# usb.net
KiCad netlist of a schematic drawn in EAGLE
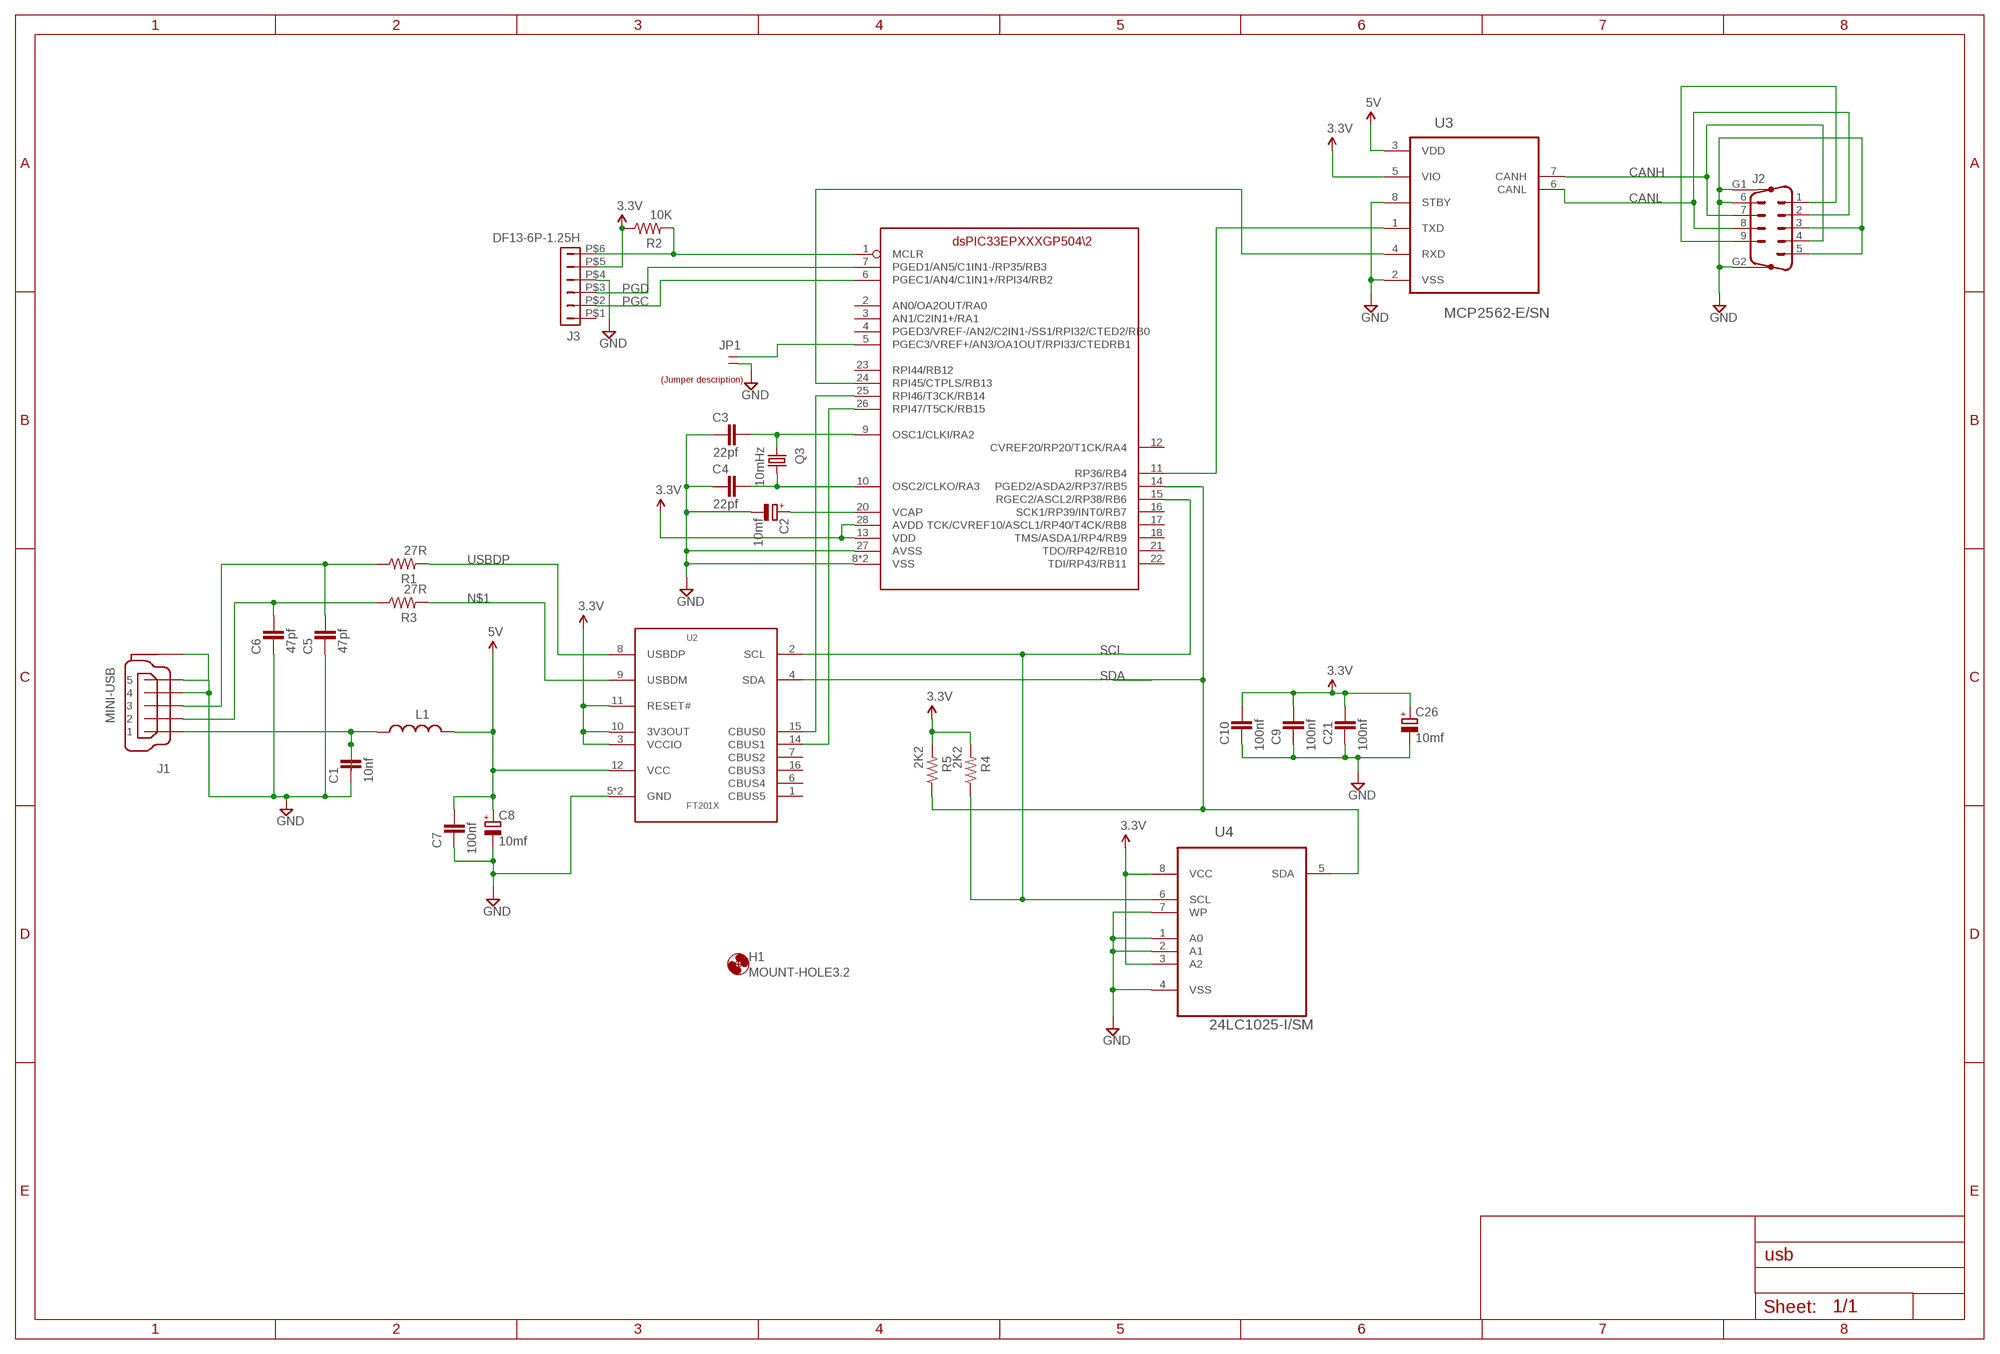
[diagram p0: schematic, sheet 1]

(export (version "E")
  (design (tool "Eeschema 10.0.6"))
  (components
    (comp (ref "C1")
      (value "10nf")
      (footprint "eagle-import:C805")
      (libsource (lib "eagle-import") (part "CAPACITOR_NPOL-0805"))
    )
    (comp (ref "C2")
      (value "10mf")
      (footprint "eagle-import:SMC_A")
      (libsource (lib "eagle-import") (part "CAPACITOR_POL-SMC_A"))
    )
    (comp (ref "C3")
      (value "22pf")
      (footprint "eagle-import:C805")
      (libsource (lib "eagle-import") (part "CAPACITOR_NPOL-0805"))
    )
    (comp (ref "C4")
      (value "22pf")
      (footprint "eagle-import:C805")
      (libsource (lib "eagle-import") (part "CAPACITOR_NPOL-0805"))
    )
    (comp (ref "C5")
      (value "47pf")
      (footprint "eagle-import:C805")
      (libsource (lib "eagle-import") (part "CAPACITOR_NPOL-0805"))
    )
    (comp (ref "C6")
      (value "47pf")
      (footprint "eagle-import:C805")
      (libsource (lib "eagle-import") (part "CAPACITOR_NPOL-0805"))
    )
    (comp (ref "C7")
      (value "100nf")
      (footprint "eagle-import:C805")
      (libsource (lib "eagle-import") (part "CAPACITOR_NPOL-0805"))
    )
    (comp (ref "C8")
      (value "10mf")
      (footprint "eagle-import:SMC_A")
      (libsource (lib "eagle-import") (part "CAPACITOR_POL-SMC_A"))
    )
    (comp (ref "C9")
      (value "100nf")
      (footprint "eagle-import:C805")
      (libsource (lib "eagle-import") (part "CAPACITOR_NPOL-0805"))
    )
    (comp (ref "C10")
      (value "100nf")
      (footprint "eagle-import:C805")
      (libsource (lib "eagle-import") (part "CAPACITOR_NPOL-0805"))
    )
    (comp (ref "C21")
      (value "100nf")
      (footprint "eagle-import:C805")
      (libsource (lib "eagle-import") (part "CAPACITOR_NPOL-0805"))
    )
    (comp (ref "C26")
      (value "10mf")
      (footprint "eagle-import:SMC_A")
      (libsource (lib "eagle-import") (part "CAPACITOR_POL-SMC_A"))
    )
    (comp (ref "H1")
      (value "MOUNT-HOLE3.2")
      (footprint "eagle-import:3,2")
      (libsource (lib "eagle-import") (part "MOUNT-HOLE3.2"))
    )
    (comp (ref "J1")
      (value "MINI-USB")
      (footprint "eagle-import:MINI-USB")
      (libsource (lib "eagle-import") (part "MINI-USB"))
    )
    (comp (ref "J2")
      (value "M09HP")
      (footprint "eagle-import:M09HP")
      (libsource (lib "eagle-import") (part "M09HP"))
    )
    (comp (ref "J3")
      (value "DF13-6P-1.25H")
      (footprint "eagle-import:DF13A-6P-1.25H")
      (libsource (lib "eagle-import") (part "DF13-6P-1.25H"))
    )
    (comp (ref "JP1")
      (value "JUMPER-1X2")
      (footprint "eagle-import:JUMPER-1X2")
      (libsource (lib "eagle-import") (part "JUMPER-1X2"))
    )
    (comp (ref "L1")
      (value "FERRITE-0603")
      (footprint "eagle-import:FB603")
      (libsource (lib "eagle-import") (part "FERRITE-0603"))
    )
    (comp (ref "Q3")
      (value "10mHz")
      (footprint "eagle-import:HC49_S")
      (fields (field (name "PARTNO") "9B-10.000MBBK-B"))
      (libsource (lib "eagle-import") (part "CRYSTALHC49S"))
    )
    (comp (ref "R1")
      (value "27R")
      (footprint "eagle-import:0603-RES")
      (fields (field (name "PARTNO") "ERJ-3GEYJ103V"))
      (libsource (lib "eagle-import") (part "RESISTOR0603-RES"))
    )
    (comp (ref "R2")
      (value "10K")
      (footprint "eagle-import:0603-RES")
      (fields (field (name "PARTNO") "ERJ-3GEYJ103V"))
      (libsource (lib "eagle-import") (part "RESISTOR0603-RES"))
    )
    (comp (ref "R3")
      (value "27R")
      (footprint "eagle-import:0603-RES")
      (fields (field (name "PARTNO") "ERJ-3GEYJ103V"))
      (libsource (lib "eagle-import") (part "RESISTOR0603-RES"))
    )
    (comp (ref "R4")
      (value "2K2")
      (footprint "eagle-import:0603-RES")
      (fields (field (name "PARTNO") "ERJ-3GEYJ103V"))
      (libsource (lib "eagle-import") (part "RESISTOR0603-RES"))
    )
    (comp (ref "R5")
      (value "2K2")
      (footprint "eagle-import:0603-RES")
      (fields (field (name "PARTNO") "ERJ-3GEYJ103V"))
      (libsource (lib "eagle-import") (part "RESISTOR0603-RES"))
    )
    (comp (ref "U$2")
      (value "LABEL_JUMPER_1X2")
      (footprint "eagle-import:JUMP2_DESC")
      (fields (field (name "OFF") "Normal") (field (name "ON") "Reset"))
      (libsource (lib "eagle-import") (part "LABEL_JUMPER_1X2"))
    )
    (comp (ref "U1")
      (value "DSPIC33EPXXXGP502")
      (footprint "eagle-import:SOIC-28")
      (libsource (lib "eagle-import") (part "DSPIC33EPXXXGP502"))
    )
    (comp (ref "U2")
      (value "FT201X")
      (footprint "eagle-import:TSSOP-16")
      (libsource (lib "eagle-import") (part "FT201X"))
    )
    (comp (ref "U3")
      (value "MCP2562-E/SN")
      (footprint "eagle-import:SOIC-8N")
      (libsource (lib "eagle-import") (part "MCP2562-E/SN"))
    )
    (comp (ref "U4")
      (value "24LC1025-I/SM")
      (footprint "eagle-import:SOIC8-N_MC")
      (libsource (lib "eagle-import") (part "24LC1025-I/SM"))
    )
  )
  (nets
    (net (code "1") (name "/CANH") (class "Default")
      (node (ref "J2") (pin "4") (pinfunction "4_4") (pintype "passive"))
      (node (ref "J2") (pin "7") (pinfunction "7_7") (pintype "passive"))
      (node (ref "U3") (pin "7") (pinfunction "CANH_7") (pintype "bidirectional"))
    )
    (net (code "2") (name "/CANL") (class "Default")
      (node (ref "J2") (pin "2") (pinfunction "2_2") (pintype "passive"))
      (node (ref "J2") (pin "8") (pinfunction "8_8") (pintype "passive"))
      (node (ref "U3") (pin "6") (pinfunction "CANL_6") (pintype "bidirectional"))
    )
    (net (code "3") (name "/N$1") (class "Default")
      (node (ref "R3") (pin "2") (pinfunction "2_2") (pintype "passive"))
      (node (ref "U2") (pin "9") (pinfunction "USBDM_9") (pintype "bidirectional"))
    )
    (net (code "4") (name "/PGC") (class "Default")
      (node (ref "J3") (pin "P$2") (pinfunction "2_P$2") (pintype "passive"))
      (node (ref "U1") (pin "6") (pinfunction "PGEC1/AN4/C1IN1+/RPI34/RB2_6") (pintype "bidirectional"))
    )
    (net (code "5") (name "/PGD") (class "Default")
      (node (ref "J3") (pin "P$3") (pinfunction "3_P$3") (pintype "passive"))
      (node (ref "U1") (pin "7") (pinfunction "PGED1/AN5/C1IN1-/RP35/RB3_7") (pintype "bidirectional"))
    )
    (net (code "6") (name "/SCL") (class "Default")
      (node (ref "R4") (pin "1") (pinfunction "1_1") (pintype "passive"))
      (node (ref "U1") (pin "15") (pinfunction "RGEC2/ASCL2/RP38/RB6_15") (pintype "bidirectional"))
      (node (ref "U2") (pin "2") (pinfunction "SCL_2") (pintype "bidirectional"))
      (node (ref "U4") (pin "6") (pinfunction "SCL_6") (pintype "input"))
    )
    (net (code "7") (name "/SDA") (class "Default")
      (node (ref "R5") (pin "1") (pinfunction "1_1") (pintype "passive"))
      (node (ref "U1") (pin "14") (pinfunction "PGED2/ASDA2/RP37/RB5_14") (pintype "bidirectional"))
      (node (ref "U2") (pin "4") (pinfunction "SDA_4") (pintype "bidirectional"))
      (node (ref "U4") (pin "5") (pinfunction "SDA_5") (pintype "bidirectional"))
    )
    (net (code "8") (name "/USBDP") (class "Default")
      (node (ref "R1") (pin "2") (pinfunction "2_2") (pintype "passive"))
      (node (ref "U2") (pin "8") (pinfunction "USBDP_8") (pintype "bidirectional"))
    )
    (net (code "9") (name "3.3V") (class "Default")
      (node (ref "C10") (pin "1") (pinfunction "1_1") (pintype "passive"))
      (node (ref "C21") (pin "1") (pinfunction "1_1") (pintype "passive"))
      (node (ref "C26") (pin "+") (pinfunction "+_+") (pintype "passive"))
      (node (ref "C9") (pin "1") (pinfunction "1_1") (pintype "passive"))
      (node (ref "J3") (pin "P$5") (pinfunction "5_P$5") (pintype "passive"))
      (node (ref "R2") (pin "1") (pinfunction "1_1") (pintype "passive"))
      (node (ref "R4") (pin "2") (pinfunction "2_2") (pintype "passive"))
      (node (ref "R5") (pin "2") (pinfunction "2_2") (pintype "passive"))
      (node (ref "U1") (pin "13") (pinfunction "VDD_13") (pintype "bidirectional"))
      (node (ref "U1") (pin "28") (pinfunction "AVDD_28") (pintype "bidirectional"))
      (node (ref "U2") (pin "10") (pinfunction "3V3OUT_10") (pintype "bidirectional"))
      (node (ref "U2") (pin "11") (pinfunction "RESET#_11") (pintype "bidirectional"))
      (node (ref "U2") (pin "3") (pinfunction "VCCIO_3") (pintype "bidirectional"))
      (node (ref "U3") (pin "5") (pinfunction "VIO_5") (pintype "power_in"))
      (node (ref "U4") (pin "3") (pinfunction "A2_3") (pintype "input"))
      (node (ref "U4") (pin "8") (pinfunction "VCC_8") (pintype "power_in"))
    )
    (net (code "10") (name "5V") (class "Default")
      (node (ref "C7") (pin "1") (pinfunction "1_1") (pintype "passive"))
      (node (ref "C8") (pin "+") (pinfunction "+_+") (pintype "passive"))
      (node (ref "L1") (pin "2") (pinfunction "2_2") (pintype "passive"))
      (node (ref "U2") (pin "12") (pinfunction "VCC_12") (pintype "bidirectional"))
      (node (ref "U3") (pin "3") (pinfunction "VDD_3") (pintype "power_in"))
    )
    (net (code "11") (name "GND") (class "Default")
      (node (ref "C1") (pin "2") (pinfunction "2_2") (pintype "passive"))
      (node (ref "C10") (pin "2") (pinfunction "2_2") (pintype "passive"))
      (node (ref "C2") (pin "-") (pinfunction "-_-") (pintype "passive"))
      (node (ref "C21") (pin "2") (pinfunction "2_2") (pintype "passive"))
      (node (ref "C26") (pin "-") (pinfunction "-_-") (pintype "passive"))
      (node (ref "C3") (pin "2") (pinfunction "2_2") (pintype "passive"))
      (node (ref "C4") (pin "2") (pinfunction "2_2") (pintype "passive"))
      (node (ref "C5") (pin "2") (pinfunction "2_2") (pintype "passive"))
      (node (ref "C6") (pin "2") (pinfunction "2_2") (pintype "passive"))
      (node (ref "C7") (pin "2") (pinfunction "2_2") (pintype "passive"))
      (node (ref "C8") (pin "-") (pinfunction "-_-") (pintype "passive"))
      (node (ref "C9") (pin "2") (pinfunction "2_2") (pintype "passive"))
      (node (ref "J1") (pin "4") (pinfunction "4_4") (pintype "input"))
      (node (ref "J1") (pin "5") (pinfunction "5_5") (pintype "input"))
      (node (ref "J1") (pin "M1") (pinfunction "MOUNT_M1") (pintype "bidirectional"))
      (node (ref "J1") (pin "M2") (pinfunction "MOUNT_M2") (pintype "bidirectional"))
      (node (ref "J1") (pin "M3") (pinfunction "MOUNT_M3") (pintype "bidirectional"))
      (node (ref "J1") (pin "M4") (pinfunction "MOUNT_M4") (pintype "bidirectional"))
      (node (ref "J2") (pin "3") (pinfunction "3_3") (pintype "passive"))
      (node (ref "J2") (pin "5") (pinfunction "5_5") (pintype "passive"))
      (node (ref "J2") (pin "6") (pinfunction "6_6") (pintype "passive"))
      (node (ref "J2") (pin "G1") (pinfunction "G1_G1") (pintype "passive"))
      (node (ref "J2") (pin "G2") (pinfunction "G2_G2") (pintype "passive"))
      (node (ref "J3") (pin "P$4") (pinfunction "4_P$4") (pintype "passive"))
      (node (ref "JP1") (pin "2") (pinfunction "2_2") (pintype "bidirectional"))
      (node (ref "U1") (pin "19") (pinfunction "VSS_19") (pintype "bidirectional"))
      (node (ref "U1") (pin "27") (pinfunction "AVSS_27") (pintype "bidirectional"))
      (node (ref "U1") (pin "8") (pinfunction "VSS_8") (pintype "bidirectional"))
      (node (ref "U2") (pin "13") (pinfunction "GND_13") (pintype "power_in"))
      (node (ref "U2") (pin "5") (pinfunction "GND_5") (pintype "power_in"))
      (node (ref "U3") (pin "2") (pinfunction "VSS_2") (pintype "power_in"))
      (node (ref "U3") (pin "8") (pinfunction "STBY_8") (pintype "input"))
      (node (ref "U4") (pin "1") (pinfunction "A0_1") (pintype "input"))
      (node (ref "U4") (pin "2") (pinfunction "A1_2") (pintype "input"))
      (node (ref "U4") (pin "4") (pinfunction "VSS_4") (pintype "passive"))
      (node (ref "U4") (pin "7") (pinfunction "WP_7") (pintype "input"))
    )
    (net (code "12") (name "Net-(C1-Pad1)") (class "Default")
      (node (ref "C1") (pin "1") (pinfunction "1_1") (pintype "passive"))
      (node (ref "J1") (pin "1") (pinfunction "1_1") (pintype "input"))
      (node (ref "L1") (pin "1") (pinfunction "1_1") (pintype "passive"))
    )
    (net (code "13") (name "Net-(C5-Pad1)") (class "Default")
      (node (ref "C5") (pin "1") (pinfunction "1_1") (pintype "passive"))
      (node (ref "J1") (pin "3") (pinfunction "3_3") (pintype "input"))
      (node (ref "R1") (pin "1") (pinfunction "1_1") (pintype "passive"))
    )
    (net (code "14") (name "Net-(C6-Pad1)") (class "Default")
      (node (ref "C6") (pin "1") (pinfunction "1_1") (pintype "passive"))
      (node (ref "J1") (pin "2") (pinfunction "2_2") (pintype "input"))
      (node (ref "R3") (pin "1") (pinfunction "1_1") (pintype "passive"))
    )
    (net (code "15") (name "Net-(J2-Pad1)") (class "Default")
      (node (ref "J2") (pin "1") (pinfunction "1_1") (pintype "passive"))
      (node (ref "J2") (pin "9") (pinfunction "9_9") (pintype "passive"))
    )
    (net (code "16") (name "Net-(J3-6)") (class "Default")
      (node (ref "J3") (pin "P$6") (pinfunction "6_P$6") (pintype "passive"))
      (node (ref "R2") (pin "2") (pinfunction "2_2") (pintype "passive"))
      (node (ref "U1") (pin "1") (pinfunction "MCLR_1") (pintype "input"))
    )
    (net (code "17") (name "Net-(U1-OSC1{slash}CLKI{slash}RA2)") (class "Default")
      (node (ref "C3") (pin "1") (pinfunction "1_1") (pintype "passive"))
      (node (ref "Q3") (pin "2") (pinfunction "2_2") (pintype "passive"))
      (node (ref "U1") (pin "9") (pinfunction "OSC1/CLKI/RA2_9") (pintype "bidirectional"))
    )
    (net (code "18") (name "Net-(U1-OSC2{slash}CLKO{slash}RA3)") (class "Default")
      (node (ref "C4") (pin "1") (pinfunction "1_1") (pintype "passive"))
      (node (ref "Q3") (pin "1") (pinfunction "1_1") (pintype "passive"))
      (node (ref "U1") (pin "10") (pinfunction "OSC2/CLKO/RA3_10") (pintype "bidirectional"))
    )
    (net (code "19") (name "Net-(U1-PGEC3{slash}VREF+{slash}AN3{slash}OA1OUT{slash}RPI33{slash}CTEDRB1)") (class "Default")
      (node (ref "JP1") (pin "1") (pinfunction "1_1") (pintype "bidirectional"))
      (node (ref "U1") (pin "5") (pinfunction "PGEC3/VREF+/AN3/OA1OUT/RPI33/CTEDRB1_5") (pintype "bidirectional"))
    )
    (net (code "20") (name "Net-(U1-RP36{slash}RB4)") (class "Default")
      (node (ref "U1") (pin "11") (pinfunction "RP36/RB4_11") (pintype "bidirectional"))
      (node (ref "U3") (pin "1") (pinfunction "TXD_1") (pintype "input"))
    )
    (net (code "21") (name "Net-(U1-RPI45{slash}CTPLS{slash}RB13)") (class "Default")
      (node (ref "U1") (pin "24") (pinfunction "RPI45/CTPLS/RB13_24") (pintype "bidirectional"))
      (node (ref "U3") (pin "4") (pinfunction "RXD_4") (pintype "output"))
    )
    (net (code "22") (name "Net-(U1-RPI46{slash}T3CK{slash}RB14)") (class "Default")
      (node (ref "U1") (pin "25") (pinfunction "RPI46/T3CK/RB14_25") (pintype "bidirectional"))
      (node (ref "U2") (pin "15") (pinfunction "CBUS0_15") (pintype "bidirectional"))
    )
    (net (code "23") (name "Net-(U1-RPI47{slash}T5CK{slash}RB15)") (class "Default")
      (node (ref "U1") (pin "26") (pinfunction "RPI47/T5CK/RB15_26") (pintype "bidirectional"))
      (node (ref "U2") (pin "14") (pinfunction "CBUS1_14") (pintype "bidirectional"))
    )
    (net (code "24") (name "Net-(U1-VCAP)") (class "Default")
      (node (ref "C2") (pin "+") (pinfunction "+_+") (pintype "passive"))
      (node (ref "U1") (pin "20") (pinfunction "VCAP_20") (pintype "bidirectional"))
    )
    (net (code "25") (name "unconnected-(J3-1-PadP$1)") (class "Default")
      (node (ref "J3") (pin "P$1") (pinfunction "1_P$1") (pintype "passive"))
    )
    (net (code "26") (name "unconnected-(U1-AN0{slash}OA2OUT{slash}RA0-Pad2)") (class "Default")
      (node (ref "U1") (pin "2") (pinfunction "AN0/OA2OUT/RA0_2") (pintype "bidirectional"))
    )
    (net (code "27") (name "unconnected-(U1-AN1{slash}C2IN1+{slash}RA1-Pad3)") (class "Default")
      (node (ref "U1") (pin "3") (pinfunction "AN1/C2IN1+/RA1_3") (pintype "bidirectional"))
    )
    (net (code "28") (name "unconnected-(U1-CVREF20{slash}RP20{slash}T1CK{slash}RA4-Pad12)") (class "Default")
      (node (ref "U1") (pin "12") (pinfunction "CVREF20/RP20/T1CK/RA4_12") (pintype "bidirectional"))
    )
    (net (code "29") (name "unconnected-(U1-PGED3{slash}VREF-{slash}AN2{slash}C2IN1-{slash}SS1{slash}RPI32{slash}CTED2{slash}RB0-Pad4)") (class "Default")
      (node (ref "U1") (pin "4") (pinfunction "PGED3/VREF-/AN2/C2IN1-/SS1/RPI32/CTED2/RB0_4") (pintype "bidirectional"))
    )
    (net (code "30") (name "unconnected-(U1-RPI44{slash}RB12-Pad23)") (class "Default")
      (node (ref "U1") (pin "23") (pinfunction "RPI44/RB12_23") (pintype "bidirectional"))
    )
    (net (code "31") (name "unconnected-(U1-SCK1{slash}RP39{slash}INT0{slash}RB7-Pad16)") (class "Default")
      (node (ref "U1") (pin "16") (pinfunction "SCK1/RP39/INT0/RB7_16") (pintype "bidirectional"))
    )
    (net (code "32") (name "unconnected-(U1-TCK{slash}CVREF10{slash}ASCL1{slash}RP40{slash}T4CK{slash}RB8-Pad17)") (class "Default")
      (node (ref "U1") (pin "17") (pinfunction "TCK/CVREF10/ASCL1/RP40/T4CK/RB8_17") (pintype "bidirectional"))
    )
    (net (code "33") (name "unconnected-(U1-TDI{slash}RP43{slash}RB11-Pad22)") (class "Default")
      (node (ref "U1") (pin "22") (pinfunction "TDI/RP43/RB11_22") (pintype "bidirectional"))
    )
    (net (code "34") (name "unconnected-(U1-TDO{slash}RP42{slash}RB10-Pad21)") (class "Default")
      (node (ref "U1") (pin "21") (pinfunction "TDO/RP42/RB10_21") (pintype "bidirectional"))
    )
    (net (code "35") (name "unconnected-(U1-TMS{slash}ASDA1{slash}RP4{slash}RB9-Pad18)") (class "Default")
      (node (ref "U1") (pin "18") (pinfunction "TMS/ASDA1/RP4/RB9_18") (pintype "bidirectional"))
    )
    (net (code "36") (name "unconnected-(U2-CBUS2-Pad7)") (class "Default")
      (node (ref "U2") (pin "7") (pinfunction "CBUS2_7") (pintype "bidirectional"))
    )
    (net (code "37") (name "unconnected-(U2-CBUS3-Pad16)") (class "Default")
      (node (ref "U2") (pin "16") (pinfunction "CBUS3_16") (pintype "bidirectional"))
    )
    (net (code "38") (name "unconnected-(U2-CBUS4-Pad6)") (class "Default")
      (node (ref "U2") (pin "6") (pinfunction "CBUS4_6") (pintype "bidirectional"))
    )
    (net (code "39") (name "unconnected-(U2-CBUS5-Pad1)") (class "Default")
      (node (ref "U2") (pin "1") (pinfunction "CBUS5_1") (pintype "bidirectional"))
    )
  )
)
